# board.net
KiCad netlist of a schematic drawn in EAGLE
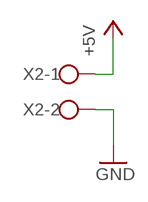
[diagram p0: schematic, sheet 1]
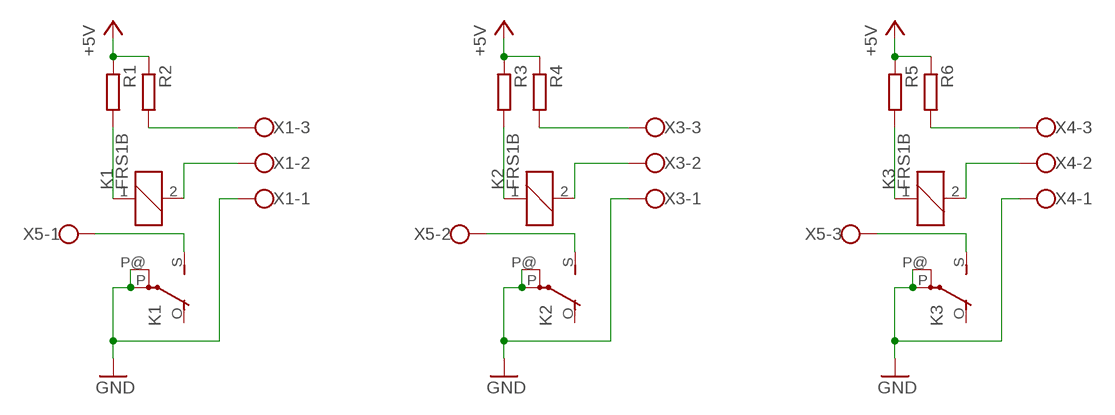
[diagram p1: schematic, sheet 2]

(export (version "E")
  (design (tool "Eeschema 10.0.6"))
  (components
    (comp (ref "K1")
      (value "FRS1B")
      (footprint "eagle-import:FRS1B")
      (libsource (lib "eagle-import") (part "FRS1B"))
    )
    (comp (ref "K2")
      (value "FRS1B")
      (footprint "eagle-import:FRS1B")
      (libsource (lib "eagle-import") (part "FRS1B"))
    )
    (comp (ref "K3")
      (value "FRS1B")
      (footprint "eagle-import:FRS1B")
      (libsource (lib "eagle-import") (part "FRS1B"))
    )
    (comp (ref "R1")
      (value "R-EU_0207/12")
      (footprint "eagle-import:0207_12")
      (libsource (lib "eagle-import") (part "R-EU_0207/12"))
    )
    (comp (ref "R2")
      (value "R-EU_0207/12")
      (footprint "eagle-import:0207_12")
      (libsource (lib "eagle-import") (part "R-EU_0207/12"))
    )
    (comp (ref "R3")
      (value "R-EU_0207/12")
      (footprint "eagle-import:0207_12")
      (libsource (lib "eagle-import") (part "R-EU_0207/12"))
    )
    (comp (ref "R4")
      (value "R-EU_0207/12")
      (footprint "eagle-import:0207_12")
      (libsource (lib "eagle-import") (part "R-EU_0207/12"))
    )
    (comp (ref "R5")
      (value "R-EU_0207/12")
      (footprint "eagle-import:0207_12")
      (libsource (lib "eagle-import") (part "R-EU_0207/12"))
    )
    (comp (ref "R6")
      (value "R-EU_0207/12")
      (footprint "eagle-import:0207_12")
      (libsource (lib "eagle-import") (part "R-EU_0207/12"))
    )
    (comp (ref "X1")
      (value "W237-103")
      (footprint "eagle-import:W237-103")
      (fields (field (name "MPN") "237-103"))
      (libsource (lib "eagle-import") (part "W237-103"))
    )
    (comp (ref "X3")
      (value "W237-103")
      (footprint "eagle-import:W237-103")
      (fields (field (name "MPN") "237-103"))
      (libsource (lib "eagle-import") (part "W237-103"))
    )
    (comp (ref "X4")
      (value "W237-103")
      (footprint "eagle-import:W237-103")
      (fields (field (name "MPN") "237-103"))
      (libsource (lib "eagle-import") (part "W237-103"))
    )
    (comp (ref "X5")
      (value "W237-103")
      (footprint "eagle-import:W237-103")
      (fields (field (name "MPN") "237-103"))
      (libsource (lib "eagle-import") (part "W237-103"))
    )
    (comp (ref "X2")
      (value "W237-102")
      (footprint "eagle-import:W237-102")
      (fields (field (name "MPN") "237-102"))
      (libsource (lib "eagle-import") (part "W237-102"))
    )
  )
  (nets
    (net (code "1") (name "+5V") (class "Default")
      (node (ref "R1") (pin "1") (pinfunction "1_1") (pintype "passive"))
      (node (ref "R2") (pin "1") (pinfunction "1_1") (pintype "passive"))
      (node (ref "R3") (pin "1") (pinfunction "1_1") (pintype "passive"))
      (node (ref "R4") (pin "1") (pinfunction "1_1") (pintype "passive"))
      (node (ref "R5") (pin "1") (pinfunction "1_1") (pintype "passive"))
      (node (ref "R6") (pin "1") (pinfunction "1_1") (pintype "passive"))
      (node (ref "X2") (pin "1") (pinfunction "KL_1") (pintype "passive"))
    )
    (net (code "2") (name "GND") (class "Default")
      (node (ref "K1") (pin "P") (pinfunction "P_P") (pintype "passive"))
      (node (ref "K1") (pin "P@") (pinfunction "P_P@") (pintype "passive"))
      (node (ref "K2") (pin "P") (pinfunction "P_P") (pintype "passive"))
      (node (ref "K2") (pin "P@") (pinfunction "P_P@") (pintype "passive"))
      (node (ref "K3") (pin "P") (pinfunction "P_P") (pintype "passive"))
      (node (ref "K3") (pin "P@") (pinfunction "P_P@") (pintype "passive"))
      (node (ref "X1") (pin "1") (pinfunction "KL_1") (pintype "passive"))
      (node (ref "X2") (pin "2") (pinfunction "KL_2") (pintype "passive"))
      (node (ref "X3") (pin "1") (pinfunction "KL_1") (pintype "passive"))
      (node (ref "X4") (pin "1") (pinfunction "KL_1") (pintype "passive"))
    )
    (net (code "3") (name "Net-(K1-Pad1)") (class "Default")
      (node (ref "K1") (pin "1") (pinfunction "1_1") (pintype "passive"))
      (node (ref "R1") (pin "2") (pinfunction "2_2") (pintype "passive"))
    )
    (net (code "4") (name "Net-(K2-Pad1)") (class "Default")
      (node (ref "K2") (pin "1") (pinfunction "1_1") (pintype "passive"))
      (node (ref "R3") (pin "2") (pinfunction "2_2") (pintype "passive"))
    )
    (net (code "5") (name "Net-(K3-Pad1)") (class "Default")
      (node (ref "K3") (pin "1") (pinfunction "1_1") (pintype "passive"))
      (node (ref "R5") (pin "2") (pinfunction "2_2") (pintype "passive"))
    )
    (net (code "6") (name "Net-(X1B-KL)") (class "Default")
      (node (ref "K1") (pin "2") (pinfunction "2_2") (pintype "passive"))
      (node (ref "X1") (pin "2") (pinfunction "KL_2") (pintype "passive"))
    )
    (net (code "7") (name "Net-(X1C-KL)") (class "Default")
      (node (ref "R2") (pin "2") (pinfunction "2_2") (pintype "passive"))
      (node (ref "X1") (pin "3") (pinfunction "KL_3") (pintype "passive"))
    )
    (net (code "8") (name "Net-(X3B-KL)") (class "Default")
      (node (ref "K2") (pin "2") (pinfunction "2_2") (pintype "passive"))
      (node (ref "X3") (pin "2") (pinfunction "KL_2") (pintype "passive"))
    )
    (net (code "9") (name "Net-(X3C-KL)") (class "Default")
      (node (ref "R4") (pin "2") (pinfunction "2_2") (pintype "passive"))
      (node (ref "X3") (pin "3") (pinfunction "KL_3") (pintype "passive"))
    )
    (net (code "10") (name "Net-(X4B-KL)") (class "Default")
      (node (ref "K3") (pin "2") (pinfunction "2_2") (pintype "passive"))
      (node (ref "X4") (pin "2") (pinfunction "KL_2") (pintype "passive"))
    )
    (net (code "11") (name "Net-(X4C-KL)") (class "Default")
      (node (ref "R6") (pin "2") (pinfunction "2_2") (pintype "passive"))
      (node (ref "X4") (pin "3") (pinfunction "KL_3") (pintype "passive"))
    )
    (net (code "12") (name "Net-(X5A-KL)") (class "Default")
      (node (ref "K1") (pin "S") (pinfunction "S_S") (pintype "passive"))
      (node (ref "X5") (pin "1") (pinfunction "KL_1") (pintype "passive"))
    )
    (net (code "13") (name "Net-(X5B-KL)") (class "Default")
      (node (ref "K2") (pin "S") (pinfunction "S_S") (pintype "passive"))
      (node (ref "X5") (pin "2") (pinfunction "KL_2") (pintype "passive"))
    )
    (net (code "14") (name "Net-(X5C-KL)") (class "Default")
      (node (ref "K3") (pin "S") (pinfunction "S_S") (pintype "passive"))
      (node (ref "X5") (pin "3") (pinfunction "KL_3") (pintype "passive"))
    )
    (net (code "15") (name "unconnected-(K1-PadO)") (class "Default")
      (node (ref "K1") (pin "O") (pinfunction "O_O") (pintype "passive"))
    )
    (net (code "16") (name "unconnected-(K2-PadO)") (class "Default")
      (node (ref "K2") (pin "O") (pinfunction "O_O") (pintype "passive"))
    )
    (net (code "17") (name "unconnected-(K3-PadO)") (class "Default")
      (node (ref "K3") (pin "O") (pinfunction "O_O") (pintype "passive"))
    )
  )
)
